# cpuledout.net
KiCad netlist of a schematic drawn in Altium Designer
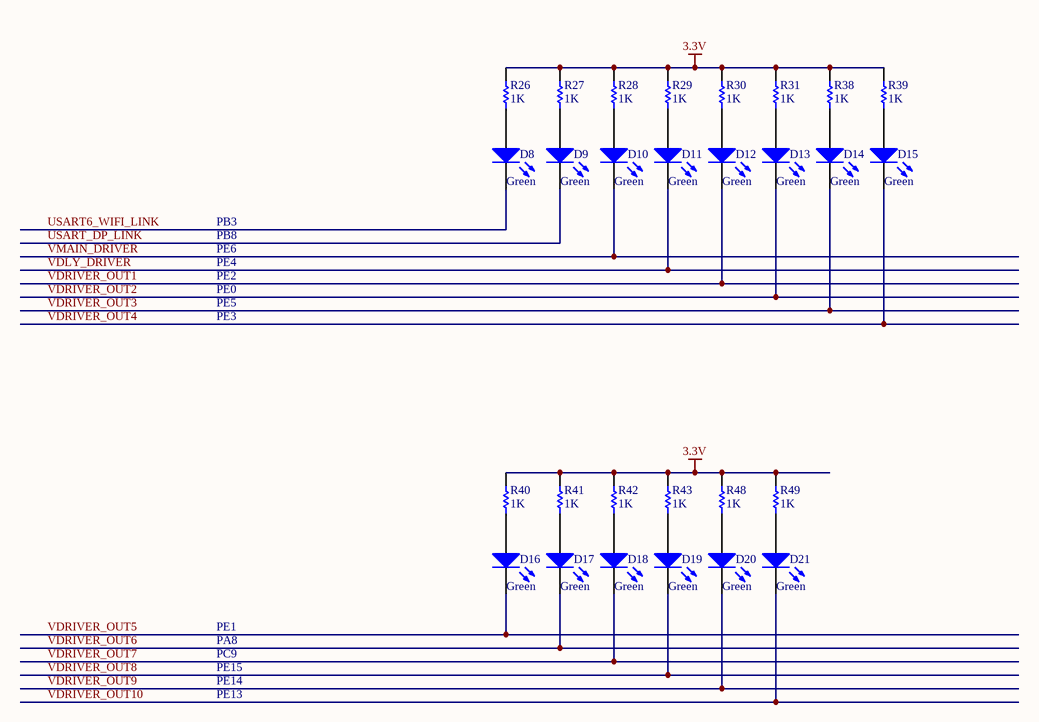
[diagram p0: cpuledout.SchDoc]

(export (version "E")
  (design (tool "Eeschema 10.0.6"))
  (components
    (comp (ref "D8")
      (value "Green")
      (footprint "CD2012-0805")
      (description "Green LED,Output indicate.")
      (fields (field (name "PUBLISHER") "Altium Limited"))
      (libsource (lib "Miscellaneous Devices") (part "LED1"))
    )
    (comp (ref "D9")
      (value "Green")
      (footprint "CD2012-0805")
      (description "Green LED,Output indicate.")
      (fields (field (name "PUBLISHER") "Altium Limited"))
      (libsource (lib "Miscellaneous Devices") (part "LED1"))
    )
    (comp (ref "D10")
      (value "Green")
      (footprint "CD2012-0805")
      (description "Green LED,Output indicate.")
      (fields (field (name "PUBLISHER") "Altium Limited"))
      (libsource (lib "Miscellaneous Devices") (part "LED1"))
    )
    (comp (ref "D11")
      (value "Green")
      (footprint "CD2012-0805")
      (description "Green LED,Output indicate.")
      (fields (field (name "PUBLISHER") "Altium Limited"))
      (libsource (lib "Miscellaneous Devices") (part "LED1"))
    )
    (comp (ref "D12")
      (value "Green")
      (footprint "CD2012-0805")
      (description "Green LED,Output indicate.")
      (fields (field (name "PUBLISHER") "Altium Limited"))
      (libsource (lib "Miscellaneous Devices") (part "LED1"))
    )
    (comp (ref "D13")
      (value "Green")
      (footprint "CD2012-0805")
      (description "Green LED,Output indicate.")
      (fields (field (name "PUBLISHER") "Altium Limited"))
      (libsource (lib "Miscellaneous Devices") (part "LED1"))
    )
    (comp (ref "D14")
      (value "Green")
      (footprint "CD2012-0805")
      (description "Green LED,Output indicate.")
      (fields (field (name "PUBLISHER") "Altium Limited"))
      (libsource (lib "Miscellaneous Devices") (part "LED1"))
    )
    (comp (ref "D15")
      (value "Green")
      (footprint "CD2012-0805")
      (description "Green LED,Output indicate.")
      (fields (field (name "PUBLISHER") "Altium Limited"))
      (libsource (lib "Miscellaneous Devices") (part "LED1"))
    )
    (comp (ref "D16")
      (value "Green")
      (footprint "CD2012-0805")
      (description "Green LED,Output indicate.")
      (fields (field (name "PUBLISHER") "Altium Limited"))
      (libsource (lib "Miscellaneous Devices") (part "LED1"))
    )
    (comp (ref "D17")
      (value "Green")
      (footprint "CD2012-0805")
      (description "Green LED,Output indicate.")
      (fields (field (name "PUBLISHER") "Altium Limited"))
      (libsource (lib "Miscellaneous Devices") (part "LED1"))
    )
    (comp (ref "D18")
      (value "Green")
      (footprint "CD2012-0805")
      (description "Green LED,Output indicate.")
      (fields (field (name "PUBLISHER") "Altium Limited"))
      (libsource (lib "Miscellaneous Devices") (part "LED1"))
    )
    (comp (ref "D19")
      (value "Green")
      (footprint "CD2012-0805")
      (description "Green LED,Output indicate.")
      (fields (field (name "PUBLISHER") "Altium Limited"))
      (libsource (lib "Miscellaneous Devices") (part "LED1"))
    )
    (comp (ref "D20")
      (value "Green")
      (footprint "CD2012-0805")
      (description "Green LED,Output indicate.")
      (fields (field (name "PUBLISHER") "Altium Limited"))
      (libsource (lib "Miscellaneous Devices") (part "LED1"))
    )
    (comp (ref "D21")
      (value "Green")
      (footprint "CD2012-0805")
      (description "Green LED,Output indicate.")
      (fields (field (name "PUBLISHER") "Altium Limited"))
      (libsource (lib "Miscellaneous Devices") (part "LED1"))
    )
    (comp (ref "R26")
      (value "1K")
      (footprint "RESC2012M")
      (description "Resistor")
      (fields (field (name "PUBLISHER") "Altium Limited"))
      (libsource (lib "Miscellaneous Devices") (part "Res1"))
    )
    (comp (ref "R27")
      (value "1K")
      (footprint "RESC2012M")
      (description "Resistor")
      (fields (field (name "PUBLISHER") "Altium Limited"))
      (libsource (lib "Miscellaneous Devices") (part "Res1"))
    )
    (comp (ref "R28")
      (value "1K")
      (footprint "RESC2012M")
      (description "Resistor")
      (fields (field (name "PUBLISHER") "Altium Limited"))
      (libsource (lib "Miscellaneous Devices") (part "Res1"))
    )
    (comp (ref "R29")
      (value "1K")
      (footprint "RESC2012M")
      (description "Resistor")
      (fields (field (name "PUBLISHER") "Altium Limited"))
      (libsource (lib "Miscellaneous Devices") (part "Res1"))
    )
    (comp (ref "R30")
      (value "1K")
      (footprint "RESC2012M")
      (description "Resistor")
      (fields (field (name "PUBLISHER") "Altium Limited"))
      (libsource (lib "Miscellaneous Devices") (part "Res1"))
    )
    (comp (ref "R31")
      (value "1K")
      (footprint "RESC2012M")
      (description "Resistor")
      (fields (field (name "PUBLISHER") "Altium Limited"))
      (libsource (lib "Miscellaneous Devices") (part "Res1"))
    )
    (comp (ref "R38")
      (value "1K")
      (footprint "RESC2012M")
      (description "Resistor")
      (fields (field (name "PUBLISHER") "Altium Limited"))
      (libsource (lib "Miscellaneous Devices") (part "Res1"))
    )
    (comp (ref "R39")
      (value "1K")
      (footprint "RESC2012M")
      (description "Resistor")
      (fields (field (name "PUBLISHER") "Altium Limited"))
      (libsource (lib "Miscellaneous Devices") (part "Res1"))
    )
    (comp (ref "R40")
      (value "1K")
      (footprint "RESC2012M")
      (description "Resistor")
      (fields (field (name "PUBLISHER") "Altium Limited"))
      (libsource (lib "Miscellaneous Devices") (part "Res1"))
    )
    (comp (ref "R41")
      (value "1K")
      (footprint "RESC2012M")
      (description "Resistor")
      (fields (field (name "PUBLISHER") "Altium Limited"))
      (libsource (lib "Miscellaneous Devices") (part "Res1"))
    )
    (comp (ref "R42")
      (value "1K")
      (footprint "RESC2012M")
      (description "Resistor")
      (fields (field (name "PUBLISHER") "Altium Limited"))
      (libsource (lib "Miscellaneous Devices") (part "Res1"))
    )
    (comp (ref "R43")
      (value "1K")
      (footprint "RESC2012M")
      (description "Resistor")
      (fields (field (name "PUBLISHER") "Altium Limited"))
      (libsource (lib "Miscellaneous Devices") (part "Res1"))
    )
    (comp (ref "R48")
      (value "1K")
      (footprint "RESC2012M")
      (description "Resistor")
      (fields (field (name "PUBLISHER") "Altium Limited"))
      (libsource (lib "Miscellaneous Devices") (part "Res1"))
    )
    (comp (ref "R49")
      (value "1K")
      (footprint "RESC2012M")
      (description "Resistor")
      (fields (field (name "PUBLISHER") "Altium Limited"))
      (libsource (lib "Miscellaneous Devices") (part "Res1"))
    )
  )
  (nets
    (net (code "1") (name "/USART6_WIFI_LINK") (class "Default")
      (node (ref "D8") (pin "2") (pinfunction "K_2") (pintype "passive"))
    )
    (net (code "2") (name "/USART_DP_LINK") (class "Default")
      (node (ref "D9") (pin "2") (pinfunction "K_2") (pintype "passive"))
    )
    (net (code "3") (name "/VDLY_DRIVER") (class "Default")
      (node (ref "D11") (pin "2") (pinfunction "K_2") (pintype "passive"))
    )
    (net (code "4") (name "/VDRIVER_OUT1") (class "Default")
      (node (ref "D12") (pin "2") (pinfunction "K_2") (pintype "passive"))
    )
    (net (code "5") (name "/VDRIVER_OUT2") (class "Default")
      (node (ref "D13") (pin "2") (pinfunction "K_2") (pintype "passive"))
    )
    (net (code "6") (name "/VDRIVER_OUT3") (class "Default")
      (node (ref "D14") (pin "2") (pinfunction "K_2") (pintype "passive"))
    )
    (net (code "7") (name "/VDRIVER_OUT4") (class "Default")
      (node (ref "D15") (pin "2") (pinfunction "K_2") (pintype "passive"))
    )
    (net (code "8") (name "/VDRIVER_OUT5") (class "Default")
      (node (ref "D16") (pin "2") (pinfunction "K_2") (pintype "passive"))
    )
    (net (code "9") (name "/VDRIVER_OUT6") (class "Default")
      (node (ref "D17") (pin "2") (pinfunction "K_2") (pintype "passive"))
    )
    (net (code "10") (name "/VDRIVER_OUT7") (class "Default")
      (node (ref "D18") (pin "2") (pinfunction "K_2") (pintype "passive"))
    )
    (net (code "11") (name "/VDRIVER_OUT8") (class "Default")
      (node (ref "D19") (pin "2") (pinfunction "K_2") (pintype "passive"))
    )
    (net (code "12") (name "/VDRIVER_OUT9") (class "Default")
      (node (ref "D20") (pin "2") (pinfunction "K_2") (pintype "passive"))
    )
    (net (code "13") (name "/VDRIVER_OUT10") (class "Default")
      (node (ref "D21") (pin "2") (pinfunction "K_2") (pintype "passive"))
    )
    (net (code "14") (name "/VMAIN_DRIVER") (class "Default")
      (node (ref "D10") (pin "2") (pinfunction "K_2") (pintype "passive"))
    )
    (net (code "15") (name "3.3V") (class "Default")
      (node (ref "R26") (pin "1") (pinfunction "1_1") (pintype "passive"))
      (node (ref "R27") (pin "1") (pinfunction "1_1") (pintype "passive"))
      (node (ref "R28") (pin "1") (pinfunction "1_1") (pintype "passive"))
      (node (ref "R29") (pin "1") (pinfunction "1_1") (pintype "passive"))
      (node (ref "R30") (pin "1") (pinfunction "1_1") (pintype "passive"))
      (node (ref "R31") (pin "1") (pinfunction "1_1") (pintype "passive"))
      (node (ref "R38") (pin "1") (pinfunction "1_1") (pintype "passive"))
      (node (ref "R39") (pin "1") (pinfunction "1_1") (pintype "passive"))
      (node (ref "R40") (pin "1") (pinfunction "1_1") (pintype "passive"))
      (node (ref "R41") (pin "1") (pinfunction "1_1") (pintype "passive"))
      (node (ref "R42") (pin "1") (pinfunction "1_1") (pintype "passive"))
      (node (ref "R43") (pin "1") (pinfunction "1_1") (pintype "passive"))
      (node (ref "R48") (pin "1") (pinfunction "1_1") (pintype "passive"))
      (node (ref "R49") (pin "1") (pinfunction "1_1") (pintype "passive"))
    )
    (net (code "16") (name "Net-(D8-A)") (class "Default")
      (node (ref "D8") (pin "1") (pinfunction "A_1") (pintype "passive"))
      (node (ref "R26") (pin "2") (pinfunction "2_2") (pintype "passive"))
    )
    (net (code "17") (name "Net-(D9-A)") (class "Default")
      (node (ref "D9") (pin "1") (pinfunction "A_1") (pintype "passive"))
      (node (ref "R27") (pin "2") (pinfunction "2_2") (pintype "passive"))
    )
    (net (code "18") (name "Net-(D10-A)") (class "Default")
      (node (ref "D10") (pin "1") (pinfunction "A_1") (pintype "passive"))
      (node (ref "R28") (pin "2") (pinfunction "2_2") (pintype "passive"))
    )
    (net (code "19") (name "Net-(D11-A)") (class "Default")
      (node (ref "D11") (pin "1") (pinfunction "A_1") (pintype "passive"))
      (node (ref "R29") (pin "2") (pinfunction "2_2") (pintype "passive"))
    )
    (net (code "20") (name "Net-(D12-A)") (class "Default")
      (node (ref "D12") (pin "1") (pinfunction "A_1") (pintype "passive"))
      (node (ref "R30") (pin "2") (pinfunction "2_2") (pintype "passive"))
    )
    (net (code "21") (name "Net-(D13-A)") (class "Default")
      (node (ref "D13") (pin "1") (pinfunction "A_1") (pintype "passive"))
      (node (ref "R31") (pin "2") (pinfunction "2_2") (pintype "passive"))
    )
    (net (code "22") (name "Net-(D14-A)") (class "Default")
      (node (ref "D14") (pin "1") (pinfunction "A_1") (pintype "passive"))
      (node (ref "R38") (pin "2") (pinfunction "2_2") (pintype "passive"))
    )
    (net (code "23") (name "Net-(D15-A)") (class "Default")
      (node (ref "D15") (pin "1") (pinfunction "A_1") (pintype "passive"))
      (node (ref "R39") (pin "2") (pinfunction "2_2") (pintype "passive"))
    )
    (net (code "24") (name "Net-(D16-A)") (class "Default")
      (node (ref "D16") (pin "1") (pinfunction "A_1") (pintype "passive"))
      (node (ref "R40") (pin "2") (pinfunction "2_2") (pintype "passive"))
    )
    (net (code "25") (name "Net-(D17-A)") (class "Default")
      (node (ref "D17") (pin "1") (pinfunction "A_1") (pintype "passive"))
      (node (ref "R41") (pin "2") (pinfunction "2_2") (pintype "passive"))
    )
    (net (code "26") (name "Net-(D18-A)") (class "Default")
      (node (ref "D18") (pin "1") (pinfunction "A_1") (pintype "passive"))
      (node (ref "R42") (pin "2") (pinfunction "2_2") (pintype "passive"))
    )
    (net (code "27") (name "Net-(D19-A)") (class "Default")
      (node (ref "D19") (pin "1") (pinfunction "A_1") (pintype "passive"))
      (node (ref "R43") (pin "2") (pinfunction "2_2") (pintype "passive"))
    )
    (net (code "28") (name "Net-(D20-A)") (class "Default")
      (node (ref "D20") (pin "1") (pinfunction "A_1") (pintype "passive"))
      (node (ref "R48") (pin "2") (pinfunction "2_2") (pintype "passive"))
    )
    (net (code "29") (name "Net-(D21-A)") (class "Default")
      (node (ref "D21") (pin "1") (pinfunction "A_1") (pintype "passive"))
      (node (ref "R49") (pin "2") (pinfunction "2_2") (pintype "passive"))
    )
  )
)
